# current_sense_shunt.net
KiCad netlist of a schematic drawn in Altium Designer
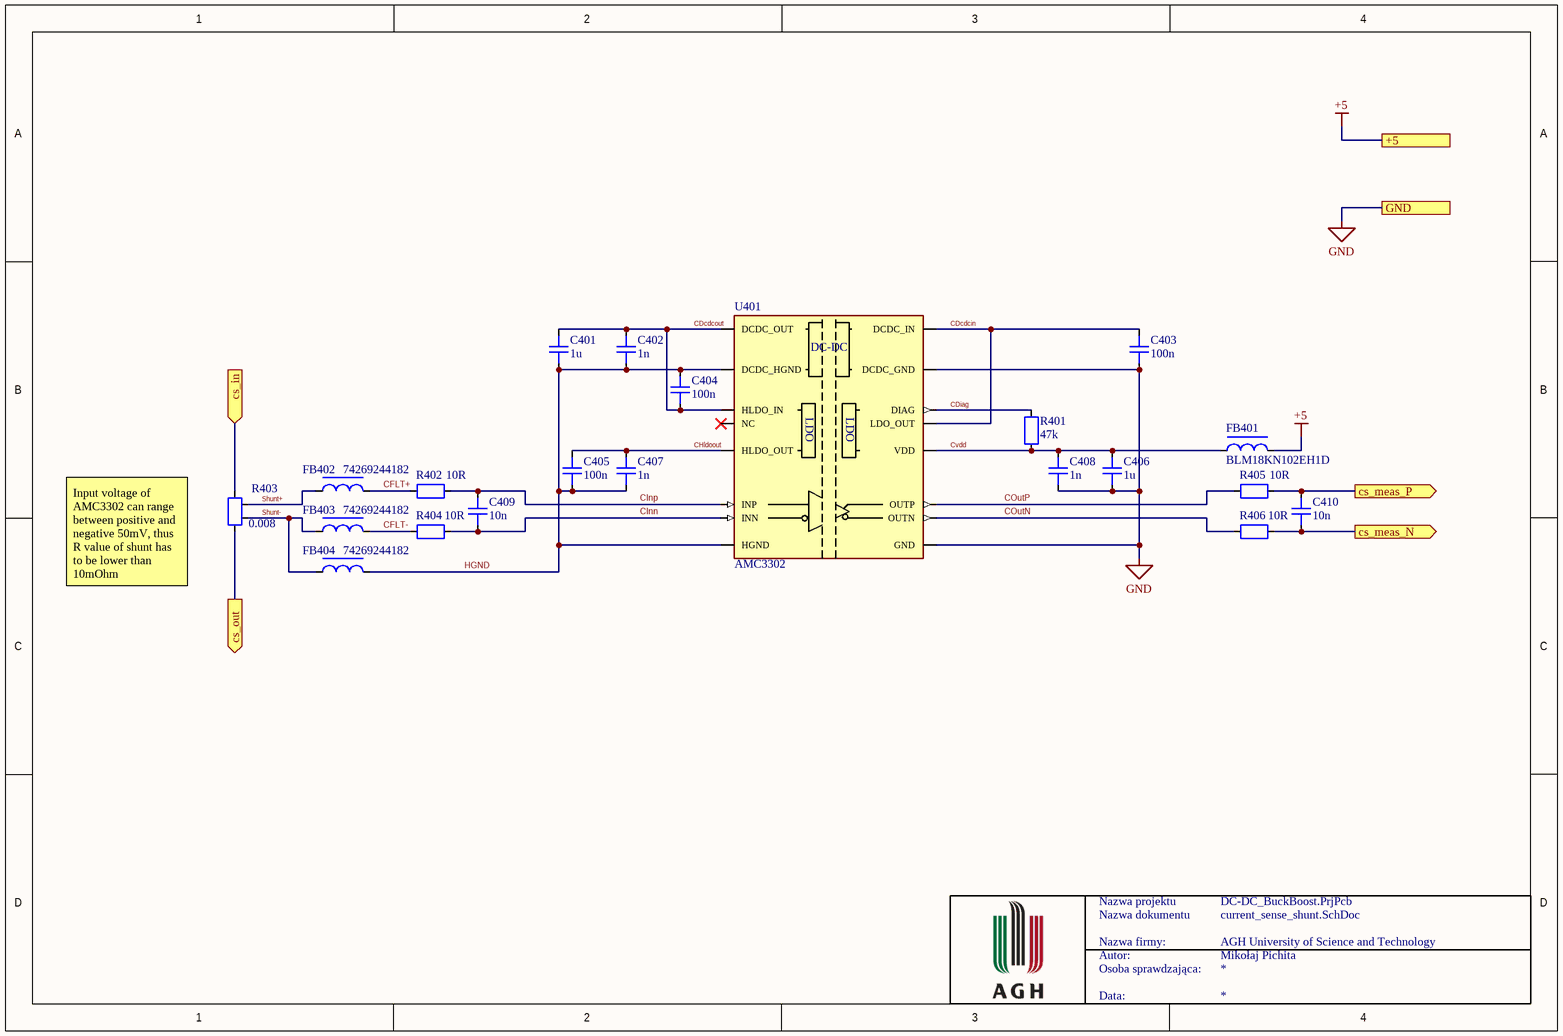
[diagram p0: current_sense_shunt.SchDoc]

(export (version "E")
  (design (tool "Eeschema 10.0.6"))
  (components
    (comp (ref "C401")
      (value "1u")
      (footprint "CAP1206")
      (libsource (lib "schematic_library") (part "Capacitor"))
    )
    (comp (ref "C402")
      (value "1n")
      (footprint "CAP0603")
      (libsource (lib "schematic_library") (part "Capacitor"))
    )
    (comp (ref "C403")
      (value "100n")
      (footprint "CAP0603")
      (libsource (lib "schematic_library") (part "Capacitor"))
    )
    (comp (ref "C404")
      (value "100n")
      (footprint "CAP0603")
      (libsource (lib "schematic_library") (part "Capacitor"))
    )
    (comp (ref "C405")
      (value "100n")
      (footprint "CAP0603")
      (libsource (lib "schematic_library") (part "Capacitor"))
    )
    (comp (ref "C406")
      (value "1u")
      (footprint "CAP1206")
      (libsource (lib "schematic_library") (part "Capacitor"))
    )
    (comp (ref "C407")
      (value "1n")
      (footprint "CAP0603")
      (libsource (lib "schematic_library") (part "Capacitor"))
    )
    (comp (ref "C408")
      (value "1n")
      (footprint "CAP1206")
      (libsource (lib "schematic_library") (part "Capacitor"))
    )
    (comp (ref "C409")
      (value "10n")
      (footprint "CAP0603")
      (libsource (lib "schematic_library") (part "Capacitor"))
    )
    (comp (ref "C410")
      (value "10n")
      (footprint "CAP0603")
      (libsource (lib "schematic_library") (part "Capacitor"))
    )
    (comp (ref "FB401")
      (value "BLM18KN102EH1D")
      (footprint "RES0603")
      (libsource (lib "") (part "Ferrite Bead_1"))
    )
    (comp (ref "FB402")
      (value "74269244182")
      (footprint "FB0402")
      (libsource (lib "schematic_library") (part "Ferrite Bead"))
    )
    (comp (ref "FB403")
      (value "74269244182")
      (footprint "FB0402")
      (libsource (lib "schematic_library") (part "Ferrite Bead"))
    )
    (comp (ref "FB404")
      (value "74269244182")
      (footprint "FB0402")
      (libsource (lib "schematic_library") (part "Ferrite Bead"))
    )
    (comp (ref "R401")
      (value "47k")
      (footprint "RES0603")
      (libsource (lib "schematic_library") (part "Resistor"))
    )
    (comp (ref "R402")
      (value "10R")
      (footprint "RES0603")
      (libsource (lib "schematic_library") (part "Resistor"))
    )
    (comp (ref "R403")
      (value "0.008")
      (footprint "WSL3637")
      (description "0.008 Ohm Current Sense Resistor")
      (libsource (lib "schematic_library") (part "Shunt resistor"))
    )
    (comp (ref "R404")
      (value "10R")
      (footprint "RES0603")
      (libsource (lib "schematic_library") (part "Resistor"))
    )
    (comp (ref "R405")
      (value "10R")
      (footprint "RES0603")
      (libsource (lib "schematic_library") (part "Resistor"))
    )
    (comp (ref "R406")
      (value "10R")
      (footprint "RES0603")
      (libsource (lib "schematic_library") (part "Resistor"))
    )
    (comp (ref "U401")
      (value "AMC3302")
      (footprint "SOIC127P1030X265-16N")
      (description "±50-mV input, precision current sensing reinforced isolated amplifier with integrated DC/DC")
      (libsource (lib "schematic_library") (part "AMC3302"))
    )
  )
  (nets
    (net (code "1") (name "+5") (class "Default") (node (ref "FB401") (pin "1") (pintype "passive")))
    (net (code "2") (name "/CDcdcin") (class "Default")
      (node (ref "C403") (pin "1") (pintype "passive"))
      (node (ref "U401") (pin "13") (pinfunction "LDO_OUT_13") (pintype "power_in"))
      (node (ref "U401") (pin "16") (pinfunction "DCDC_IN_16") (pintype "power_in"))
    )
    (net (code "3") (name "/CDcdcout") (class "Default")
      (node (ref "C401") (pin "1") (pintype "passive"))
      (node (ref "C402") (pin "1") (pintype "passive"))
      (node (ref "C404") (pin "2") (pintype "passive"))
      (node (ref "U401") (pin "1") (pinfunction "DCDC_OUT_1") (pintype "power_in"))
      (node (ref "U401") (pin "3") (pinfunction "HLDO_IN_3") (pintype "power_in"))
    )
    (net (code "4") (name "/CDiag") (class "Default")
      (node (ref "R401") (pin "1") (pintype "passive"))
      (node (ref "U401") (pin "14") (pinfunction "DIAG_14") (pintype "output"))
    )
    (net (code "5") (name "/CFLT+") (class "Default")
      (node (ref "FB402") (pin "2") (pintype "passive"))
      (node (ref "R402") (pin "2") (pintype "passive"))
    )
    (net (code "6") (name "/CFLT-") (class "Default")
      (node (ref "FB403") (pin "2") (pintype "passive"))
      (node (ref "R404") (pin "2") (pintype "passive"))
    )
    (net (code "7") (name "/CHldoout") (class "Default")
      (node (ref "C405") (pin "1") (pintype "passive"))
      (node (ref "C407") (pin "1") (pintype "passive"))
      (node (ref "U401") (pin "5") (pinfunction "HLDO_OUT_5") (pintype "power_in"))
    )
    (net (code "8") (name "/CInn") (class "Default")
      (node (ref "C409") (pin "1") (pintype "passive"))
      (node (ref "R404") (pin "1") (pintype "passive"))
      (node (ref "U401") (pin "7") (pinfunction "INN_7") (pintype "input"))
    )
    (net (code "9") (name "/CInp") (class "Default")
      (node (ref "C409") (pin "2") (pintype "passive"))
      (node (ref "R402") (pin "1") (pintype "passive"))
      (node (ref "U401") (pin "6") (pinfunction "INP_6") (pintype "input"))
    )
    (net (code "10") (name "/COutN") (class "Default")
      (node (ref "R406") (pin "2") (pintype "passive"))
      (node (ref "U401") (pin "10") (pinfunction "OUTN_10") (pintype "output"))
    )
    (net (code "11") (name "/COutP") (class "Default")
      (node (ref "R405") (pin "2") (pintype "passive"))
      (node (ref "U401") (pin "11") (pinfunction "OUTP_11") (pintype "output"))
    )
    (net (code "12") (name "/Cvdd") (class "Default")
      (node (ref "C406") (pin "1") (pintype "passive"))
      (node (ref "C408") (pin "1") (pintype "passive"))
      (node (ref "FB401") (pin "2") (pintype "passive"))
      (node (ref "R401") (pin "2") (pintype "passive"))
      (node (ref "U401") (pin "12") (pinfunction "VDD_12") (pintype "power_in"))
    )
    (net (code "13") (name "/HGND") (class "Default")
      (node (ref "C401") (pin "2") (pintype "passive"))
      (node (ref "C402") (pin "2") (pintype "passive"))
      (node (ref "C404") (pin "1") (pintype "passive"))
      (node (ref "C405") (pin "2") (pintype "passive"))
      (node (ref "C407") (pin "2") (pintype "passive"))
      (node (ref "FB404") (pin "2") (pintype "passive"))
      (node (ref "U401") (pin "2") (pinfunction "DCDC_HGND_2") (pintype "passive"))
      (node (ref "U401") (pin "8") (pinfunction "HGND_8") (pintype "passive"))
    )
    (net (code "14") (name "/Shunt+") (class "Default")
      (node (ref "FB402") (pin "1") (pintype "passive"))
      (node (ref "R403") (pin "4") (pintype "passive"))
    )
    (net (code "15") (name "/Shunt-") (class "Default")
      (node (ref "FB403") (pin "1") (pintype "passive"))
      (node (ref "FB404") (pin "1") (pintype "passive"))
      (node (ref "R403") (pin "3") (pintype "passive"))
    )
    (net (code "16") (name "/cs_in") (class "Default") (node (ref "R403") (pin "1") (pintype "passive")))
    (net (code "17") (name "/cs_meas_N") (class "Default")
      (node (ref "C410") (pin "1") (pintype "passive"))
      (node (ref "R406") (pin "1") (pintype "passive"))
    )
    (net (code "18") (name "/cs_meas_P") (class "Default")
      (node (ref "C410") (pin "2") (pintype "passive"))
      (node (ref "R405") (pin "1") (pintype "passive"))
    )
    (net (code "19") (name "/cs_out") (class "Default") (node (ref "R403") (pin "2") (pintype "passive")))
    (net (code "20") (name "GND") (class "Default")
      (node (ref "C403") (pin "2") (pintype "passive"))
      (node (ref "C406") (pin "2") (pintype "passive"))
      (node (ref "C408") (pin "2") (pintype "passive"))
      (node (ref "U401") (pin "15") (pinfunction "DCDC_GND_15") (pintype "power_in"))
      (node (ref "U401") (pin "9") (pinfunction "GND_9") (pintype "power_in"))
    )
    (net (code "21") (name "unconnected-(U401-NC-Pad4)") (class "Default")
      (node (ref "U401") (pin "4") (pinfunction "NC_4") (pintype "passive+no_connect"))
    )
  )
)
